# hd-hdr-alt.net
KiCad netlist of a schematic drawn in EAGLE
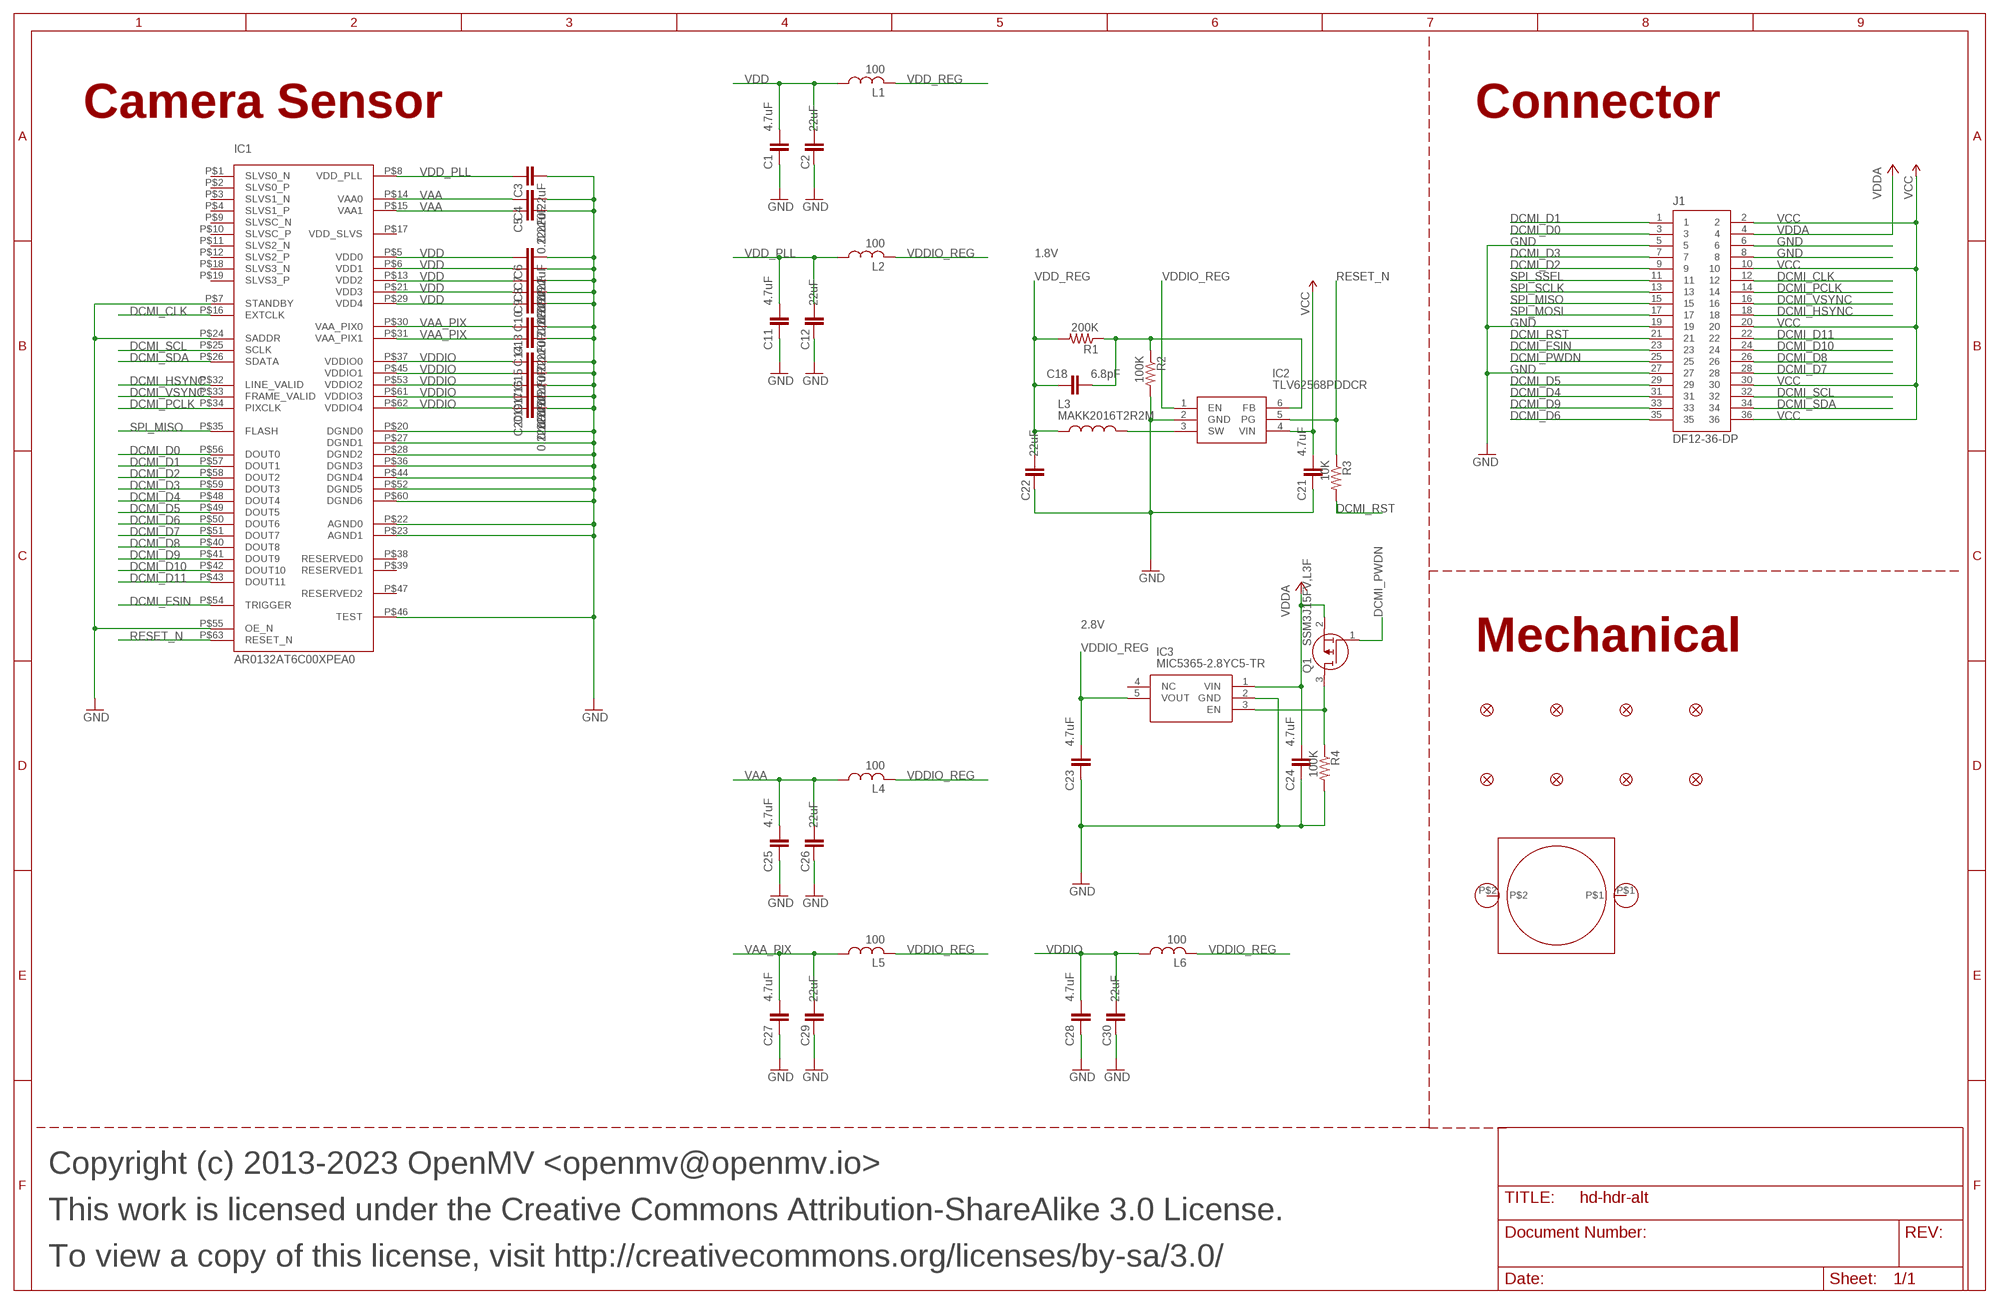
[diagram p0: schematic, sheet 1]

(export (version "E")
  (design (tool "Eeschema 10.0.6"))
  (components
    (comp (ref "C1")
      (value "4.7uF")
      (footprint "eagle-import:0402")
      (fields (field (name "MPN") "JMK105BBJ475MV-F"))
      (libsource (lib "eagle-import") (part "CAP_0402"))
    )
    (comp (ref "C2")
      (value "22uF")
      (footprint "eagle-import:0805")
      (fields (field (name "MPN") "CL21A226MQQNNNE"))
      (libsource (lib "eagle-import") (part "22UF-0805-6.3V-20%"))
    )
    (comp (ref "C3")
      (value "0.22uF")
      (footprint "eagle-import:C0201")
      (fields (field (name "MPN") "GRM033R60J224ME15D"))
      (libsource (lib "eagle-import") (part "C-EUC0201"))
    )
    (comp (ref "C4")
      (value "0.22uF")
      (footprint "eagle-import:C0201")
      (fields (field (name "MPN") "GRM033R60J224ME15D"))
      (libsource (lib "eagle-import") (part "C-EUC0201"))
    )
    (comp (ref "C5")
      (value "0.22uF")
      (footprint "eagle-import:C0201")
      (fields (field (name "MPN") "GRM033R60J224ME15D"))
      (libsource (lib "eagle-import") (part "C-EUC0201"))
    )
    (comp (ref "C6")
      (value "0.22uF")
      (footprint "eagle-import:C0201")
      (fields (field (name "MPN") "GRM033R60J224ME15D"))
      (libsource (lib "eagle-import") (part "C-EUC0201"))
    )
    (comp (ref "C7")
      (value "0.22uF")
      (footprint "eagle-import:C0201")
      (fields (field (name "MPN") "GRM033R60J224ME15D"))
      (libsource (lib "eagle-import") (part "C-EUC0201"))
    )
    (comp (ref "C8")
      (value "0.22uF")
      (footprint "eagle-import:C0201")
      (fields (field (name "MPN") "GRM033R60J224ME15D"))
      (libsource (lib "eagle-import") (part "C-EUC0201"))
    )
    (comp (ref "C9")
      (value "0.22uF")
      (footprint "eagle-import:C0201")
      (fields (field (name "MPN") "GRM033R60J224ME15D"))
      (libsource (lib "eagle-import") (part "C-EUC0201"))
    )
    (comp (ref "C10")
      (value "0.22uF")
      (footprint "eagle-import:C0201")
      (fields (field (name "MPN") "GRM033R60J224ME15D"))
      (libsource (lib "eagle-import") (part "C-EUC0201"))
    )
    (comp (ref "C11")
      (value "4.7uF")
      (footprint "eagle-import:0402")
      (fields (field (name "MPN") "JMK105BBJ475MV-F"))
      (libsource (lib "eagle-import") (part "CAP_0402"))
    )
    (comp (ref "C12")
      (value "22uF")
      (footprint "eagle-import:0805")
      (fields (field (name "MPN") "CL21A226MQQNNNE"))
      (libsource (lib "eagle-import") (part "22UF-0805-6.3V-20%"))
    )
    (comp (ref "C13")
      (value "0.22uF")
      (footprint "eagle-import:C0201")
      (fields (field (name "MPN") "GRM033R60J224ME15D"))
      (libsource (lib "eagle-import") (part "C-EUC0201"))
    )
    (comp (ref "C14")
      (value "0.22uF")
      (footprint "eagle-import:C0201")
      (fields (field (name "MPN") "GRM033R60J224ME15D"))
      (libsource (lib "eagle-import") (part "C-EUC0201"))
    )
    (comp (ref "C15")
      (value "0.22uF")
      (footprint "eagle-import:C0201")
      (fields (field (name "MPN") "GRM033R60J224ME15D"))
      (libsource (lib "eagle-import") (part "C-EUC0201"))
    )
    (comp (ref "C16")
      (value "0.22uF")
      (footprint "eagle-import:C0201")
      (fields (field (name "MPN") "GRM033R60J224ME15D"))
      (libsource (lib "eagle-import") (part "C-EUC0201"))
    )
    (comp (ref "C17")
      (value "0.22uF")
      (footprint "eagle-import:C0201")
      (fields (field (name "MPN") "GRM033R60J224ME15D"))
      (libsource (lib "eagle-import") (part "C-EUC0201"))
    )
    (comp (ref "C18")
      (value "6.8pF")
      (footprint "eagle-import:0402")
      (fields (field (name "MPN") "GRM1555C1H6R8DA01D"))
      (libsource (lib "eagle-import") (part "CAP_0402"))
    )
    (comp (ref "C19")
      (value "0.22uF")
      (footprint "eagle-import:C0201")
      (fields (field (name "MPN") "GRM033R60J224ME15D"))
      (libsource (lib "eagle-import") (part "C-EUC0201"))
    )
    (comp (ref "C20")
      (value "0.22uF")
      (footprint "eagle-import:C0201")
      (fields (field (name "MPN") "GRM033R60J224ME15D"))
      (libsource (lib "eagle-import") (part "C-EUC0201"))
    )
    (comp (ref "C21")
      (value "4.7uF")
      (footprint "eagle-import:0402")
      (fields (field (name "MPN") "JMK105BBJ475MV-F"))
      (libsource (lib "eagle-import") (part "CAP_0402"))
    )
    (comp (ref "C22")
      (value "22uF")
      (footprint "eagle-import:0805")
      (fields (field (name "MPN") "CL21A226MQQNNNE"))
      (libsource (lib "eagle-import") (part "22UF-0805-6.3V-20%"))
    )
    (comp (ref "C23")
      (value "4.7uF")
      (footprint "eagle-import:0402")
      (fields (field (name "MPN") "JMK105BBJ475MV-F"))
      (libsource (lib "eagle-import") (part "CAP_0402"))
    )
    (comp (ref "C24")
      (value "4.7uF")
      (footprint "eagle-import:0402")
      (fields (field (name "MPN") "JMK105BBJ475MV-F"))
      (libsource (lib "eagle-import") (part "CAP_0402"))
    )
    (comp (ref "C25")
      (value "4.7uF")
      (footprint "eagle-import:0402")
      (fields (field (name "MPN") "JMK105BBJ475MV-F"))
      (libsource (lib "eagle-import") (part "CAP_0402"))
    )
    (comp (ref "C26")
      (value "22uF")
      (footprint "eagle-import:0805")
      (fields (field (name "MPN") "CL21A226MQQNNNE"))
      (libsource (lib "eagle-import") (part "22UF-0805-6.3V-20%"))
    )
    (comp (ref "C27")
      (value "4.7uF")
      (footprint "eagle-import:0402")
      (fields (field (name "MPN") "JMK105BBJ475MV-F"))
      (libsource (lib "eagle-import") (part "CAP_0402"))
    )
    (comp (ref "C28")
      (value "4.7uF")
      (footprint "eagle-import:0402")
      (fields (field (name "MPN") "JMK105BBJ475MV-F"))
      (libsource (lib "eagle-import") (part "CAP_0402"))
    )
    (comp (ref "C29")
      (value "22uF")
      (footprint "eagle-import:0805")
      (fields (field (name "MPN") "CL21A226MQQNNNE"))
      (libsource (lib "eagle-import") (part "22UF-0805-6.3V-20%"))
    )
    (comp (ref "C30")
      (value "22uF")
      (footprint "eagle-import:0805")
      (fields (field (name "MPN") "CL21A226MQQNNNE"))
      (libsource (lib "eagle-import") (part "22UF-0805-6.3V-20%"))
    )
    (comp (ref "FD1")
      (value "FIDUCIAL1X2")
      (footprint "eagle-import:FIDUCIAL-1X2")
      (libsource (lib "eagle-import") (part "FIDUCIAL1X2"))
    )
    (comp (ref "FD2")
      (value "FIDUCIAL1X2")
      (footprint "eagle-import:FIDUCIAL-1X2")
      (libsource (lib "eagle-import") (part "FIDUCIAL1X2"))
    )
    (comp (ref "FD3")
      (value "FIDUCIAL1X2")
      (footprint "eagle-import:FIDUCIAL-1X2")
      (libsource (lib "eagle-import") (part "FIDUCIAL1X2"))
    )
    (comp (ref "FD4")
      (value "FIDUCIAL1X2")
      (footprint "eagle-import:FIDUCIAL-1X2")
      (libsource (lib "eagle-import") (part "FIDUCIAL1X2"))
    )
    (comp (ref "FD5")
      (value "FIDUCIAL1X2")
      (footprint "eagle-import:FIDUCIAL-1X2")
      (libsource (lib "eagle-import") (part "FIDUCIAL1X2"))
    )
    (comp (ref "FD6")
      (value "FIDUCIAL1X2")
      (footprint "eagle-import:FIDUCIAL-1X2")
      (libsource (lib "eagle-import") (part "FIDUCIAL1X2"))
    )
    (comp (ref "FD7")
      (value "FIDUCIAL1X2")
      (footprint "eagle-import:FIDUCIAL-1X2")
      (libsource (lib "eagle-import") (part "FIDUCIAL1X2"))
    )
    (comp (ref "FD8")
      (value "FIDUCIAL1X2")
      (footprint "eagle-import:FIDUCIAL-1X2")
      (libsource (lib "eagle-import") (part "FIDUCIAL1X2"))
    )
    (comp (ref "H1")
      (value "LENSMOUNT20MM")
      (footprint "eagle-import:LENSMOUNT-20MM")
      (libsource (lib "eagle-import") (part "LENSMOUNT20MM"))
    )
    (comp (ref "IC1")
      (value "AR0132AT6C00XPEA0")
      (footprint "eagle-import:AR0132AT6C00XPEA0")
      (fields (field (name "MPN") "AR0132AT6C00XPEA0-TPBR"))
      (libsource (lib "eagle-import") (part "AR0132AT6C00XPEA0"))
    )
    (comp (ref "IC2")
      (value "TLV62568PDDCR")
      (footprint "eagle-import:SOT95P280X110-6N")
      (fields (field (name "MOUSER_PART_NUMBER") "595-TLV62568PDDCR"))
      (libsource (lib "eagle-import") (part "TLV62568PDDCR"))
    )
    (comp (ref "IC3")
      (value "MIC5365-2.8YC5-TR")
      (footprint "eagle-import:SOT65P210X110-5N")
      (fields (field (name "MOUSER_PART_NUMBER") "998-MIC5365-2.8YC5TR"))
      (libsource (lib "eagle-import") (part "MIC5365-2.8YC5-TR"))
    )
    (comp (ref "J1")
      (value "DF12-36-DP")
      (footprint "eagle-import:DF12-36-DP")
      (fields (field (name "MPN") "DF12NB(3.0)-36DP-0.5V(51)"))
      (libsource (lib "eagle-import") (part "DF12-36-DP"))
    )
    (comp (ref "L1")
      (value "100")
      (footprint "eagle-import:0402")
      (fields (field (name "MPN") "MFBM1V1005-101-R"))
      (libsource (lib "eagle-import") (part "INDUCTOR_0402"))
    )
    (comp (ref "L2")
      (value "100")
      (footprint "eagle-import:0402")
      (fields (field (name "MPN") "MFBM1V1005-101-R"))
      (libsource (lib "eagle-import") (part "INDUCTOR_0402"))
    )
    (comp (ref "L3")
      (value "MAKK2016T2R2M")
      (footprint "eagle-import:INDC2016X100N")
      (fields (field (name "MF") "Taiyo Yuden"))
      (libsource (lib "eagle-import") (part "MAKK2016T2R2M"))
    )
    (comp (ref "L4")
      (value "100")
      (footprint "eagle-import:0402")
      (fields (field (name "MPN") "MFBM1V1005-101-R"))
      (libsource (lib "eagle-import") (part "INDUCTOR_0402"))
    )
    (comp (ref "L5")
      (value "100")
      (footprint "eagle-import:0402")
      (fields (field (name "MPN") "MFBM1V1005-101-R"))
      (libsource (lib "eagle-import") (part "INDUCTOR_0402"))
    )
    (comp (ref "L6")
      (value "100")
      (footprint "eagle-import:0402")
      (fields (field (name "MPN") "MFBM1V1005-101-R"))
      (libsource (lib "eagle-import") (part "INDUCTOR_0402"))
    )
    (comp (ref "Q1")
      (value "SSM3J15FV,L3F")
      (footprint "eagle-import:SSM3J15FVL3F")
      (fields (field (name "MOUSER_PART_NUMBER") "757-SSM3J15FVL3F"))
      (libsource (lib "eagle-import") (part "SSM3J15FV,L3F"))
    )
    (comp (ref "R1")
      (value "200K")
      (footprint "eagle-import:R0402")
      (fields (field (name "MPN") "CRCW0402200KFKEDC"))
      (libsource (lib "eagle-import") (part "R-US_R0402"))
    )
    (comp (ref "R2")
      (value "100K")
      (footprint "eagle-import:R0402")
      (fields (field (name "MPN") "AC0402FR-07100KL"))
      (libsource (lib "eagle-import") (part "R-US_R0402"))
    )
    (comp (ref "R3")
      (value "10K")
      (footprint "eagle-import:R0402")
      (fields (field (name "MPN") "AC0402FR-1310KL"))
      (libsource (lib "eagle-import") (part "R-US_R0402"))
    )
    (comp (ref "R4")
      (value "100K")
      (footprint "eagle-import:R0402")
      (fields (field (name "MPN") "AC0402FR-07100KL"))
      (libsource (lib "eagle-import") (part "R-US_R0402"))
    )
  )
  (nets
    (net (code "1") (name "/DCMI_CLK") (class "Default")
      (node (ref "IC1") (pin "P$16") (pinfunction "EXTCLK_P$16") (pintype "bidirectional"))
      (node (ref "J1") (pin "12") (pinfunction "12_12") (pintype "bidirectional"))
    )
    (net (code "2") (name "/DCMI_D0") (class "Default")
      (node (ref "IC1") (pin "P$56") (pinfunction "DOUT0_P$56") (pintype "bidirectional"))
      (node (ref "J1") (pin "3") (pinfunction "3_3") (pintype "bidirectional"))
    )
    (net (code "3") (name "/DCMI_D1") (class "Default")
      (node (ref "IC1") (pin "P$57") (pinfunction "DOUT1_P$57") (pintype "bidirectional"))
      (node (ref "J1") (pin "1") (pinfunction "1_1") (pintype "bidirectional"))
    )
    (net (code "4") (name "/DCMI_D2") (class "Default")
      (node (ref "IC1") (pin "P$58") (pinfunction "DOUT2_P$58") (pintype "bidirectional"))
      (node (ref "J1") (pin "9") (pinfunction "9_9") (pintype "bidirectional"))
    )
    (net (code "5") (name "/DCMI_D3") (class "Default")
      (node (ref "IC1") (pin "P$59") (pinfunction "DOUT3_P$59") (pintype "bidirectional"))
      (node (ref "J1") (pin "7") (pinfunction "7_7") (pintype "bidirectional"))
    )
    (net (code "6") (name "/DCMI_D4") (class "Default")
      (node (ref "IC1") (pin "P$48") (pinfunction "DOUT4_P$48") (pintype "bidirectional"))
      (node (ref "J1") (pin "31") (pinfunction "31_31") (pintype "bidirectional"))
    )
    (net (code "7") (name "/DCMI_D5") (class "Default")
      (node (ref "IC1") (pin "P$49") (pinfunction "DOUT5_P$49") (pintype "bidirectional"))
      (node (ref "J1") (pin "29") (pinfunction "29_29") (pintype "bidirectional"))
    )
    (net (code "8") (name "/DCMI_D6") (class "Default")
      (node (ref "IC1") (pin "P$50") (pinfunction "DOUT6_P$50") (pintype "bidirectional"))
      (node (ref "J1") (pin "35") (pinfunction "35_35") (pintype "bidirectional"))
    )
    (net (code "9") (name "/DCMI_D7") (class "Default")
      (node (ref "IC1") (pin "P$51") (pinfunction "DOUT7_P$51") (pintype "bidirectional"))
      (node (ref "J1") (pin "28") (pinfunction "28_28") (pintype "bidirectional"))
    )
    (net (code "10") (name "/DCMI_D8") (class "Default")
      (node (ref "IC1") (pin "P$40") (pinfunction "DOUT8_P$40") (pintype "bidirectional"))
      (node (ref "J1") (pin "26") (pinfunction "26_26") (pintype "bidirectional"))
    )
    (net (code "11") (name "/DCMI_D9") (class "Default")
      (node (ref "IC1") (pin "P$41") (pinfunction "DOUT9_P$41") (pintype "bidirectional"))
      (node (ref "J1") (pin "33") (pinfunction "33_33") (pintype "bidirectional"))
    )
    (net (code "12") (name "/DCMI_D10") (class "Default")
      (node (ref "IC1") (pin "P$42") (pinfunction "DOUT10_P$42") (pintype "bidirectional"))
      (node (ref "J1") (pin "24") (pinfunction "24_24") (pintype "bidirectional"))
    )
    (net (code "13") (name "/DCMI_D11") (class "Default")
      (node (ref "IC1") (pin "P$43") (pinfunction "DOUT11_P$43") (pintype "bidirectional"))
      (node (ref "J1") (pin "22") (pinfunction "22_22") (pintype "bidirectional"))
    )
    (net (code "14") (name "/DCMI_FSIN") (class "Default")
      (node (ref "IC1") (pin "P$54") (pinfunction "TRIGGER_P$54") (pintype "bidirectional"))
      (node (ref "J1") (pin "23") (pinfunction "23_23") (pintype "bidirectional"))
    )
    (net (code "15") (name "/DCMI_HSYNC") (class "Default")
      (node (ref "IC1") (pin "P$32") (pinfunction "LINE_VALID_P$32") (pintype "bidirectional"))
      (node (ref "J1") (pin "18") (pinfunction "18_18") (pintype "bidirectional"))
    )
    (net (code "16") (name "/DCMI_PCLK") (class "Default")
      (node (ref "IC1") (pin "P$34") (pinfunction "PIXCLK_P$34") (pintype "bidirectional"))
      (node (ref "J1") (pin "14") (pinfunction "14_14") (pintype "bidirectional"))
    )
    (net (code "17") (name "/DCMI_PWDN") (class "Default")
      (node (ref "J1") (pin "25") (pinfunction "25_25") (pintype "bidirectional"))
      (node (ref "Q1") (pin "1") (pinfunction "G_1") (pintype "bidirectional"))
    )
    (net (code "18") (name "/DCMI_RST") (class "Default")
      (node (ref "J1") (pin "21") (pinfunction "21_21") (pintype "bidirectional"))
      (node (ref "R3") (pin "2") (pinfunction "2_2") (pintype "passive"))
    )
    (net (code "19") (name "/DCMI_SCL") (class "Default")
      (node (ref "IC1") (pin "P$25") (pinfunction "SCLK_P$25") (pintype "bidirectional"))
      (node (ref "J1") (pin "32") (pinfunction "32_32") (pintype "bidirectional"))
    )
    (net (code "20") (name "/DCMI_SDA") (class "Default")
      (node (ref "IC1") (pin "P$26") (pinfunction "SDATA_P$26") (pintype "bidirectional"))
      (node (ref "J1") (pin "34") (pinfunction "34_34") (pintype "bidirectional"))
    )
    (net (code "21") (name "/DCMI_VSYNC") (class "Default")
      (node (ref "IC1") (pin "P$33") (pinfunction "FRAME_VALID_P$33") (pintype "bidirectional"))
      (node (ref "J1") (pin "16") (pinfunction "16_16") (pintype "bidirectional"))
    )
    (net (code "22") (name "/P$1") (class "Default")
      (node (ref "H1") (pin "P$1") (pinfunction "P$1_P$1") (pintype "power_in"))
    )
    (net (code "23") (name "/P$2") (class "Default")
      (node (ref "H1") (pin "P$2") (pinfunction "P$2_P$2") (pintype "power_in"))
    )
    (net (code "24") (name "/RESET_N") (class "Default")
      (node (ref "IC1") (pin "P$63") (pinfunction "RESET_N_P$63") (pintype "bidirectional"))
      (node (ref "IC2") (pin "5") (pinfunction "PG_5") (pintype "bidirectional"))
      (node (ref "R3") (pin "1") (pinfunction "1_1") (pintype "passive"))
    )
    (net (code "25") (name "/SPI_MISO") (class "Default")
      (node (ref "IC1") (pin "P$35") (pinfunction "FLASH_P$35") (pintype "bidirectional"))
      (node (ref "J1") (pin "15") (pinfunction "15_15") (pintype "bidirectional"))
    )
    (net (code "26") (name "/SPI_MOSI") (class "Default")
      (node (ref "J1") (pin "17") (pinfunction "17_17") (pintype "bidirectional"))
    )
    (net (code "27") (name "/SPI_SCLK") (class "Default")
      (node (ref "J1") (pin "13") (pinfunction "13_13") (pintype "bidirectional"))
    )
    (net (code "28") (name "/SPI_SSEL") (class "Default")
      (node (ref "J1") (pin "11") (pinfunction "11_11") (pintype "bidirectional"))
    )
    (net (code "29") (name "/VAA") (class "Default")
      (node (ref "C25") (pin "2") (pinfunction "2_2") (pintype "passive"))
      (node (ref "C26") (pin "2") (pinfunction "2_2") (pintype "passive"))
      (node (ref "C4") (pin "1") (pinfunction "1_1") (pintype "passive"))
      (node (ref "C5") (pin "1") (pinfunction "1_1") (pintype "passive"))
      (node (ref "IC1") (pin "P$14") (pinfunction "VAA0_P$14") (pintype "bidirectional"))
      (node (ref "IC1") (pin "P$15") (pinfunction "VAA1_P$15") (pintype "bidirectional"))
      (node (ref "L4") (pin "1") (pinfunction "P$1_1") (pintype "passive"))
    )
    (net (code "30") (name "/VAA_PIX") (class "Default")
      (node (ref "C13") (pin "1") (pinfunction "1_1") (pintype "passive"))
      (node (ref "C14") (pin "1") (pinfunction "1_1") (pintype "passive"))
      (node (ref "C27") (pin "2") (pinfunction "2_2") (pintype "passive"))
      (node (ref "C29") (pin "2") (pinfunction "2_2") (pintype "passive"))
      (node (ref "IC1") (pin "P$30") (pinfunction "VAA_PIX0_P$30") (pintype "bidirectional"))
      (node (ref "IC1") (pin "P$31") (pinfunction "VAA_PIX1_P$31") (pintype "bidirectional"))
      (node (ref "L5") (pin "1") (pinfunction "P$1_1") (pintype "passive"))
    )
    (net (code "31") (name "/VDD") (class "Default")
      (node (ref "C1") (pin "2") (pinfunction "2_2") (pintype "passive"))
      (node (ref "C10") (pin "1") (pinfunction "1_1") (pintype "passive"))
      (node (ref "C2") (pin "2") (pinfunction "2_2") (pintype "passive"))
      (node (ref "C6") (pin "1") (pinfunction "1_1") (pintype "passive"))
      (node (ref "C7") (pin "1") (pinfunction "1_1") (pintype "passive"))
      (node (ref "C8") (pin "1") (pinfunction "1_1") (pintype "passive"))
      (node (ref "C9") (pin "1") (pinfunction "1_1") (pintype "passive"))
      (node (ref "IC1") (pin "P$13") (pinfunction "VDD2_P$13") (pintype "bidirectional"))
      (node (ref "IC1") (pin "P$21") (pinfunction "VDD3_P$21") (pintype "bidirectional"))
      (node (ref "IC1") (pin "P$29") (pinfunction "VDD4_P$29") (pintype "bidirectional"))
      (node (ref "IC1") (pin "P$5") (pinfunction "VDD0_P$5") (pintype "bidirectional"))
      (node (ref "IC1") (pin "P$6") (pinfunction "VDD1_P$6") (pintype "bidirectional"))
      (node (ref "L1") (pin "1") (pinfunction "P$1_1") (pintype "passive"))
    )
    (net (code "32") (name "/VDDIO") (class "Default")
      (node (ref "C15") (pin "1") (pinfunction "1_1") (pintype "passive"))
      (node (ref "C16") (pin "1") (pinfunction "1_1") (pintype "passive"))
      (node (ref "C17") (pin "1") (pinfunction "1_1") (pintype "passive"))
      (node (ref "C19") (pin "1") (pinfunction "1_1") (pintype "passive"))
      (node (ref "C20") (pin "1") (pinfunction "1_1") (pintype "passive"))
      (node (ref "C28") (pin "2") (pinfunction "2_2") (pintype "passive"))
      (node (ref "C30") (pin "2") (pinfunction "2_2") (pintype "passive"))
      (node (ref "IC1") (pin "P$37") (pinfunction "VDDIO0_P$37") (pintype "bidirectional"))
      (node (ref "IC1") (pin "P$45") (pinfunction "VDDIO1_P$45") (pintype "bidirectional"))
      (node (ref "IC1") (pin "P$53") (pinfunction "VDDIO2_P$53") (pintype "bidirectional"))
      (node (ref "IC1") (pin "P$61") (pinfunction "VDDIO3_P$61") (pintype "bidirectional"))
      (node (ref "IC1") (pin "P$62") (pinfunction "VDDIO4_P$62") (pintype "bidirectional"))
      (node (ref "L6") (pin "1") (pinfunction "P$1_1") (pintype "passive"))
    )
    (net (code "33") (name "/VDDIO_REG") (class "Default")
      (node (ref "C23") (pin "2") (pinfunction "2_2") (pintype "passive"))
      (node (ref "IC2") (pin "1") (pinfunction "EN_1") (pintype "bidirectional"))
      (node (ref "IC3") (pin "5") (pinfunction "VOUT_5") (pintype "bidirectional"))
      (node (ref "L2") (pin "2") (pinfunction "P$2_2") (pintype "passive"))
      (node (ref "L4") (pin "2") (pinfunction "P$2_2") (pintype "passive"))
      (node (ref "L5") (pin "2") (pinfunction "P$2_2") (pintype "passive"))
      (node (ref "L6") (pin "2") (pinfunction "P$2_2") (pintype "passive"))
    )
    (net (code "34") (name "/VDD_PLL") (class "Default")
      (node (ref "C11") (pin "2") (pinfunction "2_2") (pintype "passive"))
      (node (ref "C12") (pin "2") (pinfunction "2_2") (pintype "passive"))
      (node (ref "C3") (pin "1") (pinfunction "1_1") (pintype "passive"))
      (node (ref "IC1") (pin "P$8") (pinfunction "VDD_PLL_P$8") (pintype "bidirectional"))
      (node (ref "L2") (pin "1") (pinfunction "P$1_1") (pintype "passive"))
    )
    (net (code "35") (name "/VDD_REG") (class "Default")
      (node (ref "C18") (pin "1") (pinfunction "1_1") (pintype "passive"))
      (node (ref "C22") (pin "2") (pinfunction "2_2") (pintype "passive"))
      (node (ref "L1") (pin "2") (pinfunction "P$2_2") (pintype "passive"))
      (node (ref "L3") (pin "1") (pinfunction "1_1") (pintype "passive"))
      (node (ref "R1") (pin "2") (pinfunction "2_2") (pintype "passive"))
    )
    (net (code "36") (name "GND") (class "Default")
      (node (ref "C1") (pin "1") (pinfunction "1_1") (pintype "passive"))
      (node (ref "C10") (pin "2") (pinfunction "2_2") (pintype "passive"))
      (node (ref "C11") (pin "1") (pinfunction "1_1") (pintype "passive"))
      (node (ref "C12") (pin "1") (pinfunction "1_1") (pintype "passive"))
      (node (ref "C13") (pin "2") (pinfunction "2_2") (pintype "passive"))
      (node (ref "C14") (pin "2") (pinfunction "2_2") (pintype "passive"))
      (node (ref "C15") (pin "2") (pinfunction "2_2") (pintype "passive"))
      (node (ref "C16") (pin "2") (pinfunction "2_2") (pintype "passive"))
      (node (ref "C17") (pin "2") (pinfunction "2_2") (pintype "passive"))
      (node (ref "C19") (pin "2") (pinfunction "2_2") (pintype "passive"))
      (node (ref "C2") (pin "1") (pinfunction "1_1") (pintype "passive"))
      (node (ref "C20") (pin "2") (pinfunction "2_2") (pintype "passive"))
      (node (ref "C21") (pin "1") (pinfunction "1_1") (pintype "passive"))
      (node (ref "C22") (pin "1") (pinfunction "1_1") (pintype "passive"))
      (node (ref "C23") (pin "1") (pinfunction "1_1") (pintype "passive"))
      (node (ref "C24") (pin "1") (pinfunction "1_1") (pintype "passive"))
      (node (ref "C25") (pin "1") (pinfunction "1_1") (pintype "passive"))
      (node (ref "C26") (pin "1") (pinfunction "1_1") (pintype "passive"))
      (node (ref "C27") (pin "1") (pinfunction "1_1") (pintype "passive"))
      (node (ref "C28") (pin "1") (pinfunction "1_1") (pintype "passive"))
      (node (ref "C29") (pin "1") (pinfunction "1_1") (pintype "passive"))
      (node (ref "C3") (pin "2") (pinfunction "2_2") (pintype "passive"))
      (node (ref "C30") (pin "1") (pinfunction "1_1") (pintype "passive"))
      (node (ref "C4") (pin "2") (pinfunction "2_2") (pintype "passive"))
      (node (ref "C5") (pin "2") (pinfunction "2_2") (pintype "passive"))
      (node (ref "C6") (pin "2") (pinfunction "2_2") (pintype "passive"))
      (node (ref "C7") (pin "2") (pinfunction "2_2") (pintype "passive"))
      (node (ref "C8") (pin "2") (pinfunction "2_2") (pintype "passive"))
      (node (ref "C9") (pin "2") (pinfunction "2_2") (pintype "passive"))
      (node (ref "IC1") (pin "P$20") (pinfunction "DGND0_P$20") (pintype "bidirectional"))
      (node (ref "IC1") (pin "P$22") (pinfunction "AGND0_P$22") (pintype "bidirectional"))
      (node (ref "IC1") (pin "P$23") (pinfunction "AGND1_P$23") (pintype "bidirectional"))
      (node (ref "IC1") (pin "P$24") (pinfunction "SADDR_P$24") (pintype "bidirectional"))
      (node (ref "IC1") (pin "P$27") (pinfunction "DGND1_P$27") (pintype "bidirectional"))
      (node (ref "IC1") (pin "P$28") (pinfunction "DGND2_P$28") (pintype "bidirectional"))
      (node (ref "IC1") (pin "P$36") (pinfunction "DGND3_P$36") (pintype "bidirectional"))
      (node (ref "IC1") (pin "P$44") (pinfunction "DGND4_P$44") (pintype "bidirectional"))
      (node (ref "IC1") (pin "P$46") (pinfunction "TEST_P$46") (pintype "bidirectional"))
      (node (ref "IC1") (pin "P$52") (pinfunction "DGND5_P$52") (pintype "bidirectional"))
      (node (ref "IC1") (pin "P$55") (pinfunction "OE_N_P$55") (pintype "bidirectional"))
      (node (ref "IC1") (pin "P$60") (pinfunction "DGND6_P$60") (pintype "bidirectional"))
      (node (ref "IC1") (pin "P$7") (pinfunction "STANDBY_P$7") (pintype "bidirectional"))
      (node (ref "IC2") (pin "2") (pinfunction "GND_2") (pintype "bidirectional"))
      (node (ref "IC3") (pin "2") (pinfunction "GND_2") (pintype "bidirectional"))
      (node (ref "J1") (pin "19") (pinfunction "19_19") (pintype "bidirectional"))
      (node (ref "J1") (pin "27") (pinfunction "27_27") (pintype "bidirectional"))
      (node (ref "J1") (pin "5") (pinfunction "5_5") (pintype "bidirectional"))
      (node (ref "J1") (pin "6") (pinfunction "6_6") (pintype "bidirectional"))
      (node (ref "J1") (pin "8") (pinfunction "8_8") (pintype "bidirectional"))
      (node (ref "R2") (pin "2") (pinfunction "2_2") (pintype "passive"))
      (node (ref "R4") (pin "2") (pinfunction "2_2") (pintype "passive"))
    )
    (net (code "37") (name "Net-(IC2-FB)") (class "Default")
      (node (ref "C18") (pin "2") (pinfunction "2_2") (pintype "passive"))
      (node (ref "IC2") (pin "6") (pinfunction "FB_6") (pintype "bidirectional"))
      (node (ref "R1") (pin "1") (pinfunction "1_1") (pintype "passive"))
      (node (ref "R2") (pin "1") (pinfunction "1_1") (pintype "passive"))
    )
    (net (code "38") (name "Net-(IC2-SW)") (class "Default")
      (node (ref "IC2") (pin "3") (pinfunction "SW_3") (pintype "bidirectional"))
      (node (ref "L3") (pin "2") (pinfunction "2_2") (pintype "passive"))
    )
    (net (code "39") (name "Net-(IC3-EN)") (class "Default")
      (node (ref "IC3") (pin "3") (pinfunction "EN_3") (pintype "bidirectional"))
      (node (ref "Q1") (pin "3") (pinfunction "D_3") (pintype "bidirectional"))
      (node (ref "R4") (pin "1") (pinfunction "1_1") (pintype "passive"))
    )
    (net (code "40") (name "VCC") (class "Default")
      (node (ref "C21") (pin "2") (pinfunction "2_2") (pintype "passive"))
      (node (ref "IC2") (pin "4") (pinfunction "VIN_4") (pintype "bidirectional"))
      (node (ref "J1") (pin "10") (pinfunction "10_10") (pintype "bidirectional"))
      (node (ref "J1") (pin "2") (pinfunction "2_2") (pintype "bidirectional"))
      (node (ref "J1") (pin "20") (pinfunction "20_20") (pintype "bidirectional"))
      (node (ref "J1") (pin "30") (pinfunction "30_30") (pintype "bidirectional"))
      (node (ref "J1") (pin "36") (pinfunction "36_36") (pintype "bidirectional"))
    )
    (net (code "41") (name "VDDA") (class "Default")
      (node (ref "C24") (pin "2") (pinfunction "2_2") (pintype "passive"))
      (node (ref "IC3") (pin "1") (pinfunction "VIN_1") (pintype "bidirectional"))
      (node (ref "J1") (pin "4") (pinfunction "4_4") (pintype "bidirectional"))
      (node (ref "Q1") (pin "2") (pinfunction "S_2") (pintype "bidirectional"))
    )
    (net (code "42") (name "unconnected-(IC1-RESERVED0-PadP$38)") (class "Default")
      (node (ref "IC1") (pin "P$38") (pinfunction "RESERVED0_P$38") (pintype "bidirectional"))
    )
    (net (code "43") (name "unconnected-(IC1-RESERVED1-PadP$39)") (class "Default")
      (node (ref "IC1") (pin "P$39") (pinfunction "RESERVED1_P$39") (pintype "bidirectional"))
    )
    (net (code "44") (name "unconnected-(IC1-RESERVED2-PadP$47)") (class "Default")
      (node (ref "IC1") (pin "P$47") (pinfunction "RESERVED2_P$47") (pintype "bidirectional"))
    )
    (net (code "45") (name "unconnected-(IC1-SLVS0_N-PadP$1)") (class "Default")
      (node (ref "IC1") (pin "P$1") (pinfunction "SLVS0_N_P$1") (pintype "bidirectional"))
    )
    (net (code "46") (name "unconnected-(IC1-SLVS0_P-PadP$2)") (class "Default")
      (node (ref "IC1") (pin "P$2") (pinfunction "SLVS0_P_P$2") (pintype "bidirectional"))
    )
    (net (code "47") (name "unconnected-(IC1-SLVS1_N-PadP$3)") (class "Default")
      (node (ref "IC1") (pin "P$3") (pinfunction "SLVS1_N_P$3") (pintype "bidirectional"))
    )
    (net (code "48") (name "unconnected-(IC1-SLVS1_P-PadP$4)") (class "Default")
      (node (ref "IC1") (pin "P$4") (pinfunction "SLVS1_P_P$4") (pintype "bidirectional"))
    )
    (net (code "49") (name "unconnected-(IC1-SLVS2_N-PadP$11)") (class "Default")
      (node (ref "IC1") (pin "P$11") (pinfunction "SLVS2_N_P$11") (pintype "bidirectional"))
    )
    (net (code "50") (name "unconnected-(IC1-SLVS2_P-PadP$12)") (class "Default")
      (node (ref "IC1") (pin "P$12") (pinfunction "SLVS2_P_P$12") (pintype "bidirectional"))
    )
    (net (code "51") (name "unconnected-(IC1-SLVS3_N-PadP$18)") (class "Default")
      (node (ref "IC1") (pin "P$18") (pinfunction "SLVS3_N_P$18") (pintype "bidirectional"))
    )
    (net (code "52") (name "unconnected-(IC1-SLVS3_P-PadP$19)") (class "Default")
      (node (ref "IC1") (pin "P$19") (pinfunction "SLVS3_P_P$19") (pintype "bidirectional"))
    )
    (net (code "53") (name "unconnected-(IC1-SLVSC_N-PadP$9)") (class "Default")
      (node (ref "IC1") (pin "P$9") (pinfunction "SLVSC_N_P$9") (pintype "bidirectional"))
    )
    (net (code "54") (name "unconnected-(IC1-SLVSC_P-PadP$10)") (class "Default")
      (node (ref "IC1") (pin "P$10") (pinfunction "SLVSC_P_P$10") (pintype "bidirectional"))
    )
    (net (code "55") (name "unconnected-(IC1-VDD_SLVS-PadP$17)") (class "Default")
      (node (ref "IC1") (pin "P$17") (pinfunction "VDD_SLVS_P$17") (pintype "bidirectional"))
    )
    (net (code "56") (name "unconnected-(IC3-NC-Pad4)") (class "Default")
      (node (ref "IC3") (pin "4") (pinfunction "NC_4") (pintype "no_connect"))
    )
  )
)
